# Microcore_dip16_1.net
KiCad netlist of a schematic drawn in EAGLE
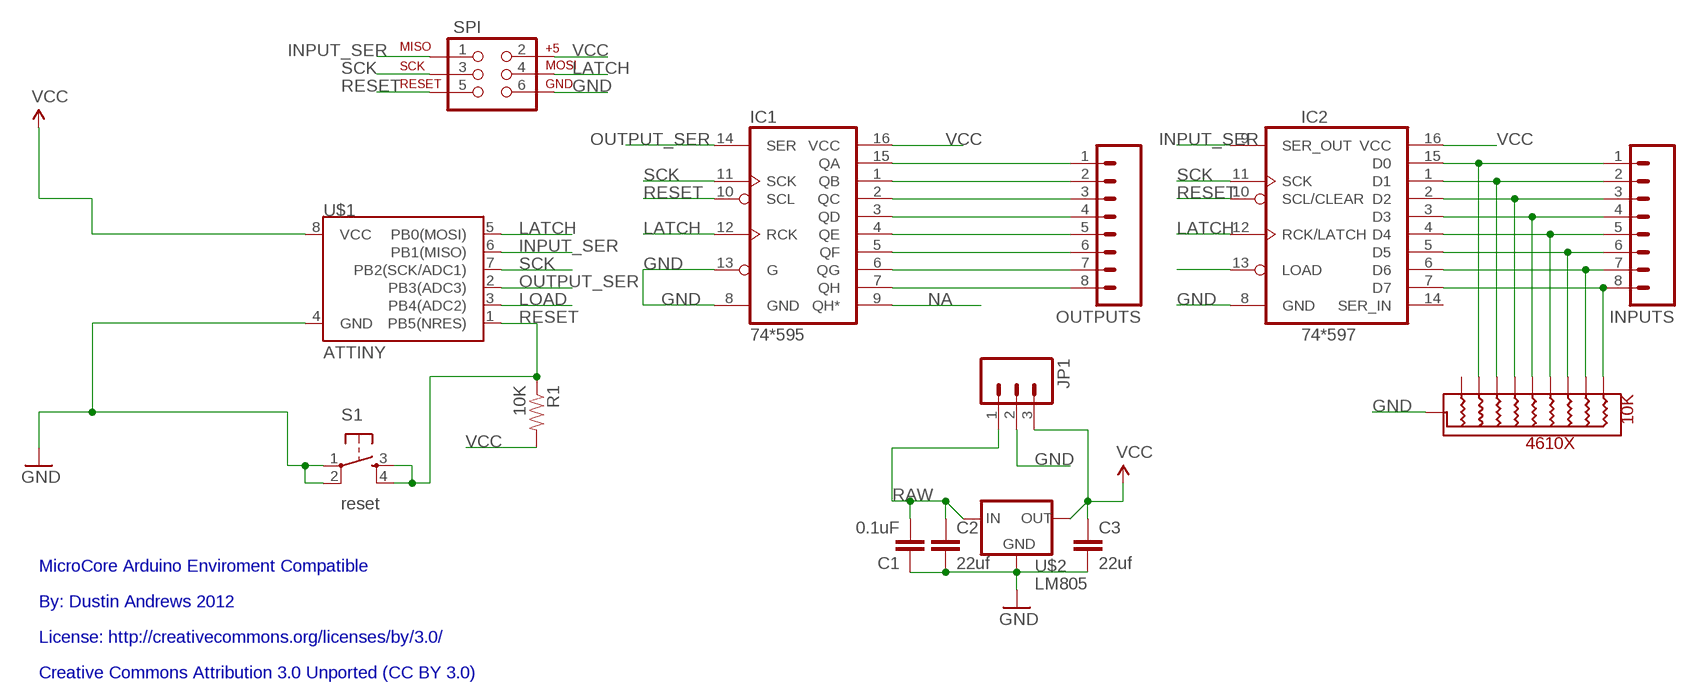
[diagram p0: schematic, sheet 1]

(export (version "E")
  (design (tool "Eeschema 10.0.6"))
  (components
    (comp (ref "10K")
      (value "4610X")
      (footprint "eagle-import:10-SIP")
      (libsource (lib "eagle-import") (part "4610X"))
    )
    (comp (ref "C1")
      (value "0.1uF")
      (footprint "eagle-import:CAP-PTH-SMALL")
      (libsource (lib "eagle-import") (part "CAPPTH"))
    )
    (comp (ref "C2")
      (value "22uf")
      (footprint "eagle-import:CAP-PTH-SMALL")
      (libsource (lib "eagle-import") (part "CAPPTH"))
    )
    (comp (ref "C3")
      (value "22uf")
      (footprint "eagle-import:CAP-PTH-SMALL")
      (libsource (lib "eagle-import") (part "CAPPTH"))
    )
    (comp (ref "IC1")
      (value "74*595")
      (footprint "eagle-import:DIL16")
      (libsource (lib "eagle-import") (part "74595NLS"))
    )
    (comp (ref "IC2")
      (value "74*597")
      (footprint "eagle-import:DIL16")
      (libsource (lib "eagle-import") (part "7459716DIP"))
    )
    (comp (ref "INPUTS")
      (value "M08LONGPADS")
      (footprint "eagle-import:1X08_LONGPADS")
      (libsource (lib "eagle-import") (part "M08LONGPADS"))
    )
    (comp (ref "JP1")
      (value "M03PTH")
      (footprint "eagle-import:1X03")
      (libsource (lib "eagle-import") (part "M03PTH"))
    )
    (comp (ref "OUTPUTS")
      (value "M08LONGPADS")
      (footprint "eagle-import:1X08_LONGPADS")
      (libsource (lib "eagle-import") (part "M08LONGPADS"))
    )
    (comp (ref "R1")
      (value "10K")
      (footprint "eagle-import:AXIAL-0.4")
      (libsource (lib "eagle-import") (part "RESISTORPTH-1/4W"))
    )
    (comp (ref "S1")
      (value "reset")
      (footprint "eagle-import:TACTILE-PTH")
      (libsource (lib "eagle-import") (part "TAC_SWITCHPTH"))
    )
    (comp (ref "SPI")
      (value "AVR_SPI_PRG_6NS")
      (footprint "eagle-import:2X3-NS")
      (libsource (lib "eagle-import") (part "AVR_SPI_PRG_6NS"))
    )
    (comp (ref "U$1")
      (value "ATTINY")
      (footprint "eagle-import:DIP08")
      (libsource (lib "eagle-import") (part "ATTINY13DIP"))
    )
    (comp (ref "U$2")
      (value "LM805")
      (footprint "eagle-import:TO220-IGO")
      (libsource (lib "eagle-import") (part "V_REG_78XXSINK"))
    )
  )
  (nets
    (net (code "1") (name "/INPUT_SER") (class "Default")
      (node (ref "IC2") (pin "9") (pinfunction "SER_OUT_9") (pintype "input"))
      (node (ref "SPI") (pin "1") (pinfunction "1_1") (pintype "passive"))
      (node (ref "U$1") (pin "6") (pinfunction "PB1(MISO)_6") (pintype "bidirectional"))
    )
    (net (code "2") (name "/LATCH") (class "Default")
      (node (ref "IC1") (pin "12") (pinfunction "RCK_12") (pintype "input"))
      (node (ref "IC2") (pin "12") (pinfunction "RCK/LATCH_12") (pintype "input"))
      (node (ref "SPI") (pin "4") (pinfunction "4_4") (pintype "passive"))
      (node (ref "U$1") (pin "5") (pinfunction "PB0(MOSI)_5") (pintype "bidirectional"))
    )
    (net (code "3") (name "/LOAD") (class "Default")
      (node (ref "IC2") (pin "13") (pinfunction "LOAD_13") (pintype "input"))
      (node (ref "U$1") (pin "3") (pinfunction "PB4(ADC2)_3") (pintype "bidirectional"))
    )
    (net (code "4") (name "/NA") (class "Default")
      (node (ref "IC1") (pin "9") (pinfunction "QH*_9") (pintype "tri_state"))
    )
    (net (code "5") (name "/OUTPUT_SER") (class "Default")
      (node (ref "IC1") (pin "14") (pinfunction "SER_14") (pintype "input"))
      (node (ref "U$1") (pin "2") (pinfunction "PB3(ADC3)_2") (pintype "bidirectional"))
    )
    (net (code "6") (name "/RAW") (class "Default")
      (node (ref "C1") (pin "2") (pinfunction "2_2") (pintype "passive"))
      (node (ref "C2") (pin "1") (pinfunction "1_1") (pintype "passive"))
      (node (ref "JP1") (pin "1") (pinfunction "1_1") (pintype "passive"))
      (node (ref "U$2") (pin "IN") (pinfunction "IN_IN") (pintype "input"))
    )
    (net (code "7") (name "/RESET") (class "Default")
      (node (ref "IC1") (pin "10") (pinfunction "SCL_10") (pintype "input"))
      (node (ref "IC2") (pin "10") (pinfunction "SCL/CLEAR_10") (pintype "input"))
      (node (ref "R1") (pin "P$1") (pinfunction "1_P$1") (pintype "passive"))
      (node (ref "S1") (pin "3") (pinfunction "3_3") (pintype "passive"))
      (node (ref "S1") (pin "4") (pinfunction "4_4") (pintype "passive"))
      (node (ref "SPI") (pin "5") (pinfunction "5_5") (pintype "passive"))
      (node (ref "U$1") (pin "1") (pinfunction "PB5(NRES)_1") (pintype "bidirectional"))
    )
    (net (code "8") (name "/SCK") (class "Default")
      (node (ref "IC1") (pin "11") (pinfunction "SCK_11") (pintype "input"))
      (node (ref "IC2") (pin "11") (pinfunction "SCK_11") (pintype "input"))
      (node (ref "SPI") (pin "3") (pinfunction "3_3") (pintype "passive"))
      (node (ref "U$1") (pin "7") (pinfunction "PB2(SCK/ADC1)_7") (pintype "bidirectional"))
    )
    (net (code "9") (name "GND") (class "Default")
      (node (ref "10K") (pin "P$1") (pinfunction "GND_P$1") (pintype "bidirectional"))
      (node (ref "C1") (pin "1") (pinfunction "1_1") (pintype "passive"))
      (node (ref "C2") (pin "2") (pinfunction "2_2") (pintype "passive"))
      (node (ref "C3") (pin "2") (pinfunction "2_2") (pintype "passive"))
      (node (ref "IC1") (pin "13") (pinfunction "G_13") (pintype "input"))
      (node (ref "IC1") (pin "8") (pinfunction "GND_8") (pintype "power_in"))
      (node (ref "IC2") (pin "8") (pinfunction "GND_8") (pintype "power_in"))
      (node (ref "JP1") (pin "2") (pinfunction "2_2") (pintype "passive"))
      (node (ref "S1") (pin "1") (pinfunction "1_1") (pintype "passive"))
      (node (ref "S1") (pin "2") (pinfunction "2_2") (pintype "passive"))
      (node (ref "SPI") (pin "6") (pinfunction "6_6") (pintype "passive"))
      (node (ref "U$1") (pin "4") (pinfunction "GND_4") (pintype "bidirectional"))
      (node (ref "U$2") (pin "GND") (pinfunction "GND_GND") (pintype "input"))
    )
    (net (code "10") (name "Net-(10K-2)") (class "Default")
      (node (ref "10K") (pin "P$3") (pinfunction "2_P$3") (pintype "bidirectional"))
      (node (ref "IC2") (pin "15") (pinfunction "D0_15") (pintype "tri_state"))
      (node (ref "INPUTS") (pin "1") (pinfunction "1_1") (pintype "passive"))
    )
    (net (code "11") (name "Net-(10K-3)") (class "Default")
      (node (ref "10K") (pin "P$4") (pinfunction "3_P$4") (pintype "bidirectional"))
      (node (ref "IC2") (pin "1") (pinfunction "D1_1") (pintype "tri_state"))
      (node (ref "INPUTS") (pin "2") (pinfunction "2_2") (pintype "passive"))
    )
    (net (code "12") (name "Net-(10K-4)") (class "Default")
      (node (ref "10K") (pin "P$5") (pinfunction "4_P$5") (pintype "bidirectional"))
      (node (ref "IC2") (pin "2") (pinfunction "D2_2") (pintype "tri_state"))
      (node (ref "INPUTS") (pin "3") (pinfunction "3_3") (pintype "passive"))
    )
    (net (code "13") (name "Net-(10K-5)") (class "Default")
      (node (ref "10K") (pin "P$6") (pinfunction "5_P$6") (pintype "bidirectional"))
      (node (ref "IC2") (pin "3") (pinfunction "D3_3") (pintype "tri_state"))
      (node (ref "INPUTS") (pin "4") (pinfunction "4_4") (pintype "passive"))
    )
    (net (code "14") (name "Net-(10K-6)") (class "Default")
      (node (ref "10K") (pin "P$7") (pinfunction "6_P$7") (pintype "bidirectional"))
      (node (ref "IC2") (pin "4") (pinfunction "D4_4") (pintype "tri_state"))
      (node (ref "INPUTS") (pin "5") (pinfunction "5_5") (pintype "passive"))
    )
    (net (code "15") (name "Net-(10K-7)") (class "Default")
      (node (ref "10K") (pin "P$8") (pinfunction "7_P$8") (pintype "bidirectional"))
      (node (ref "IC2") (pin "5") (pinfunction "D5_5") (pintype "tri_state"))
      (node (ref "INPUTS") (pin "6") (pinfunction "6_6") (pintype "passive"))
    )
    (net (code "16") (name "Net-(10K-8)") (class "Default")
      (node (ref "10K") (pin "P$9") (pinfunction "8_P$9") (pintype "bidirectional"))
      (node (ref "IC2") (pin "6") (pinfunction "D6_6") (pintype "tri_state"))
      (node (ref "INPUTS") (pin "7") (pinfunction "7_7") (pintype "passive"))
    )
    (net (code "17") (name "Net-(10K-9)") (class "Default")
      (node (ref "10K") (pin "P$10") (pinfunction "9_P$10") (pintype "bidirectional"))
      (node (ref "IC2") (pin "7") (pinfunction "D7_7") (pintype "tri_state"))
      (node (ref "INPUTS") (pin "8") (pinfunction "8_8") (pintype "passive"))
    )
    (net (code "18") (name "Net-(IC1-QA)") (class "Default")
      (node (ref "IC1") (pin "15") (pinfunction "QA_15") (pintype "tri_state"))
      (node (ref "OUTPUTS") (pin "1") (pinfunction "1_1") (pintype "passive"))
    )
    (net (code "19") (name "Net-(IC1-QB)") (class "Default")
      (node (ref "IC1") (pin "1") (pinfunction "QB_1") (pintype "tri_state"))
      (node (ref "OUTPUTS") (pin "2") (pinfunction "2_2") (pintype "passive"))
    )
    (net (code "20") (name "Net-(IC1-QC)") (class "Default")
      (node (ref "IC1") (pin "2") (pinfunction "QC_2") (pintype "tri_state"))
      (node (ref "OUTPUTS") (pin "3") (pinfunction "3_3") (pintype "passive"))
    )
    (net (code "21") (name "Net-(IC1-QD)") (class "Default")
      (node (ref "IC1") (pin "3") (pinfunction "QD_3") (pintype "tri_state"))
      (node (ref "OUTPUTS") (pin "4") (pinfunction "4_4") (pintype "passive"))
    )
    (net (code "22") (name "Net-(IC1-QE)") (class "Default")
      (node (ref "IC1") (pin "4") (pinfunction "QE_4") (pintype "tri_state"))
      (node (ref "OUTPUTS") (pin "5") (pinfunction "5_5") (pintype "passive"))
    )
    (net (code "23") (name "Net-(IC1-QF)") (class "Default")
      (node (ref "IC1") (pin "5") (pinfunction "QF_5") (pintype "tri_state"))
      (node (ref "OUTPUTS") (pin "6") (pinfunction "6_6") (pintype "passive"))
    )
    (net (code "24") (name "Net-(IC1-QG)") (class "Default")
      (node (ref "IC1") (pin "6") (pinfunction "QG_6") (pintype "tri_state"))
      (node (ref "OUTPUTS") (pin "7") (pinfunction "7_7") (pintype "passive"))
    )
    (net (code "25") (name "Net-(IC1-QH)") (class "Default")
      (node (ref "IC1") (pin "7") (pinfunction "QH_7") (pintype "tri_state"))
      (node (ref "OUTPUTS") (pin "8") (pinfunction "8_8") (pintype "passive"))
    )
    (net (code "26") (name "VCC") (class "Default")
      (node (ref "C3") (pin "1") (pinfunction "1_1") (pintype "passive"))
      (node (ref "IC1") (pin "16") (pinfunction "VCC_16") (pintype "power_in"))
      (node (ref "IC2") (pin "16") (pinfunction "VCC_16") (pintype "power_in"))
      (node (ref "JP1") (pin "3") (pinfunction "3_3") (pintype "passive"))
      (node (ref "R1") (pin "P$2") (pinfunction "2_P$2") (pintype "passive"))
      (node (ref "SPI") (pin "2") (pinfunction "2_2") (pintype "passive"))
      (node (ref "U$1") (pin "8") (pinfunction "VCC_8") (pintype "bidirectional"))
      (node (ref "U$2") (pin "OUT") (pinfunction "OUT_OUT") (pintype "output"))
    )
    (net (code "27") (name "unconnected-(10K-1-PadP$2)") (class "Default")
      (node (ref "10K") (pin "P$2") (pinfunction "1_P$2") (pintype "bidirectional"))
    )
    (net (code "28") (name "unconnected-(IC2-SER_IN-Pad14)") (class "Default")
      (node (ref "IC2") (pin "14") (pinfunction "SER_IN_14") (pintype "tri_state"))
    )
  )
)
